# INTERNAL_VCC.net
KiCad netlist of a schematic drawn in EAGLE
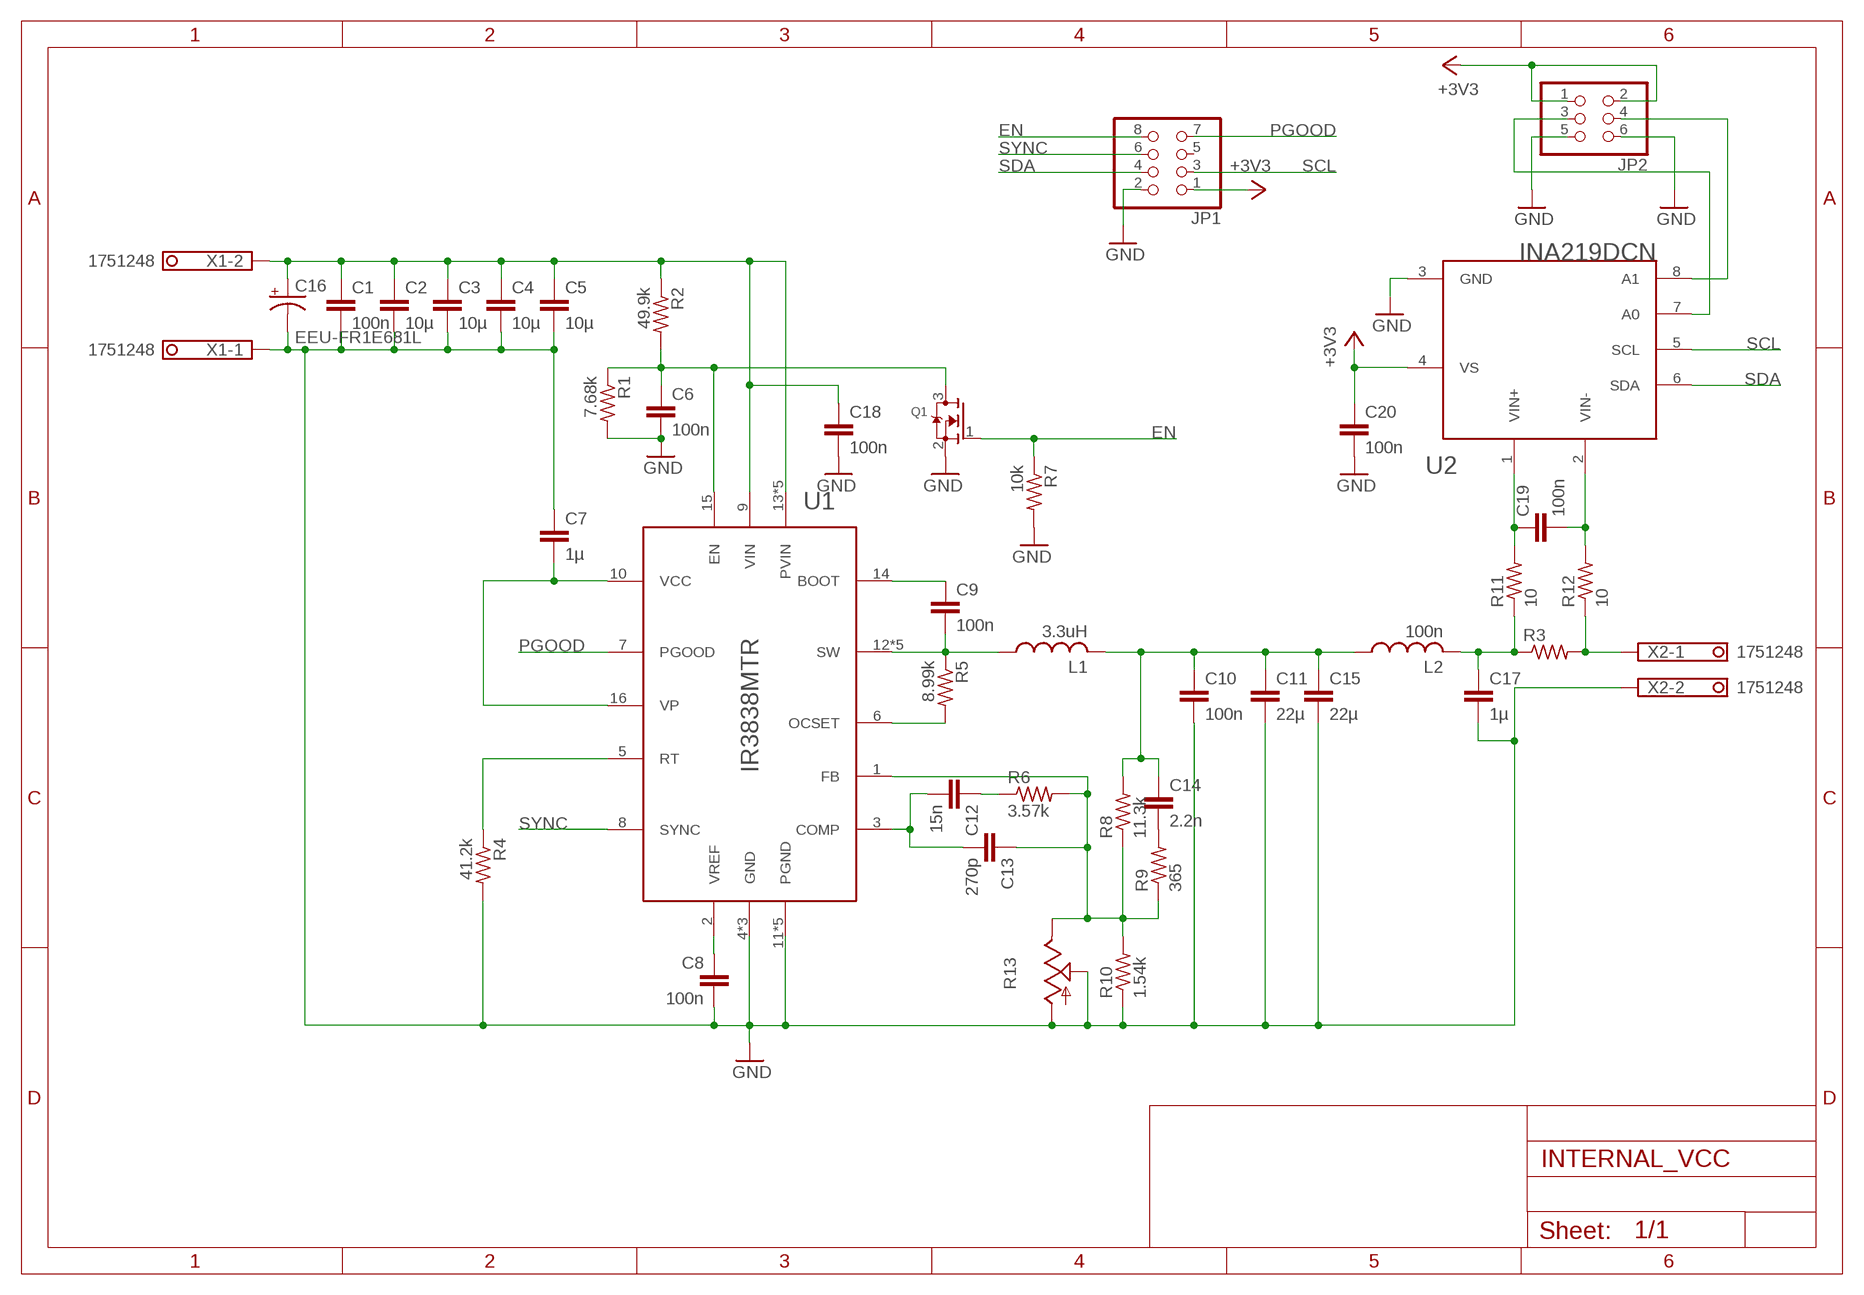
[diagram p0: schematic, sheet 1]

(export (version "E")
  (design (tool "Eeschema 10.0.6"))
  (components
    (comp (ref "C1")
      (value "100n")
      (footprint "eagle-import:C0603")
      (libsource (lib "eagle-import") (part "C-EUC0603"))
    )
    (comp (ref "C2")
      (value "10µ")
      (footprint "eagle-import:C1206")
      (libsource (lib "eagle-import") (part "C-EUC1206"))
    )
    (comp (ref "C3")
      (value "10µ")
      (footprint "eagle-import:C1206")
      (libsource (lib "eagle-import") (part "C-EUC1206"))
    )
    (comp (ref "C4")
      (value "10µ")
      (footprint "eagle-import:C1206")
      (libsource (lib "eagle-import") (part "C-EUC1206"))
    )
    (comp (ref "C5")
      (value "10µ")
      (footprint "eagle-import:C1206")
      (libsource (lib "eagle-import") (part "C-EUC1206"))
    )
    (comp (ref "C6")
      (value "100n")
      (footprint "eagle-import:C0603")
      (libsource (lib "eagle-import") (part "C-EUC0603"))
    )
    (comp (ref "C7")
      (value "1µ")
      (footprint "eagle-import:C0603")
      (libsource (lib "eagle-import") (part "C-EUC0603"))
    )
    (comp (ref "C8")
      (value "100n")
      (footprint "eagle-import:C0603")
      (libsource (lib "eagle-import") (part "C-EUC0603"))
    )
    (comp (ref "C9")
      (value "100n")
      (footprint "eagle-import:C0603")
      (libsource (lib "eagle-import") (part "C-EUC0603"))
    )
    (comp (ref "C10")
      (value "100n")
      (footprint "eagle-import:C0603")
      (libsource (lib "eagle-import") (part "C-EUC0603"))
    )
    (comp (ref "C11")
      (value "22µ")
      (footprint "eagle-import:C1210")
      (libsource (lib "eagle-import") (part "C-EUC1210"))
    )
    (comp (ref "C12")
      (value "15n")
      (footprint "eagle-import:C0603")
      (libsource (lib "eagle-import") (part "C-EUC0603"))
    )
    (comp (ref "C13")
      (value "270p")
      (footprint "eagle-import:C0603")
      (libsource (lib "eagle-import") (part "C-EUC0603"))
    )
    (comp (ref "C14")
      (value "2.2n")
      (footprint "eagle-import:C0603")
      (libsource (lib "eagle-import") (part "C-EUC0603"))
    )
    (comp (ref "C15")
      (value "22µ")
      (footprint "eagle-import:C1210")
      (libsource (lib "eagle-import") (part "C-EUC1210"))
    )
    (comp (ref "C16")
      (value "EEU-FR1E681L")
      (footprint "eagle-import:E3,5-8")
      (libsource (lib "eagle-import") (part "CPOL-USE3.5-8"))
    )
    (comp (ref "C17")
      (value "1µ")
      (footprint "eagle-import:C0603")
      (libsource (lib "eagle-import") (part "C-EUC0603"))
    )
    (comp (ref "C18")
      (value "100n")
      (footprint "eagle-import:C0603")
      (libsource (lib "eagle-import") (part "C-EUC0603"))
    )
    (comp (ref "C19")
      (value "100n")
      (footprint "eagle-import:C0603")
      (libsource (lib "eagle-import") (part "C-EUC0603"))
    )
    (comp (ref "C20")
      (value "100n")
      (footprint "eagle-import:C0603")
      (libsource (lib "eagle-import") (part "C-EUC0603"))
    )
    (comp (ref "JP1")
      (value "PINHD-2X4/90")
      (footprint "eagle-import:2X04_90")
      (libsource (lib "eagle-import") (part "PINHD-2X4/90"))
    )
    (comp (ref "JP2")
      (value "PINHD-2X3")
      (footprint "eagle-import:2X03")
      (libsource (lib "eagle-import") (part "PINHD-2X3"))
    )
    (comp (ref "L1")
      (value "3.3uH")
      (footprint "eagle-import:XAL7070")
      (libsource (lib "eagle-import") (part "L-USXAL7070"))
    )
    (comp (ref "L2")
      (value "100n")
      (footprint "eagle-import:SRP5030CA")
      (libsource (lib "eagle-import") (part "L-USSRP5030CA"))
    )
    (comp (ref "Q1")
      (value "MOSFET-NREFLOW")
      (footprint "eagle-import:SOT23")
      (libsource (lib "eagle-import") (part "MOSFET-NREFLOW"))
    )
    (comp (ref "R1")
      (value "7.68k")
      (footprint "eagle-import:R0603")
      (libsource (lib "eagle-import") (part "R-US_R0603"))
    )
    (comp (ref "R2")
      (value "49.9k")
      (footprint "eagle-import:R0603")
      (libsource (lib "eagle-import") (part "R-US_R0603"))
    )
    (comp (ref "R3")
      (value "R-US_R2010")
      (footprint "eagle-import:R2010")
      (libsource (lib "eagle-import") (part "R-US_R2010"))
    )
    (comp (ref "R4")
      (value "41.2k")
      (footprint "eagle-import:R0603")
      (libsource (lib "eagle-import") (part "R-US_R0603"))
    )
    (comp (ref "R5")
      (value "8.99k")
      (footprint "eagle-import:R0603")
      (libsource (lib "eagle-import") (part "R-US_R0603"))
    )
    (comp (ref "R6")
      (value "3.57k")
      (footprint "eagle-import:R0603")
      (libsource (lib "eagle-import") (part "R-US_R0603"))
    )
    (comp (ref "R7")
      (value "10k")
      (footprint "eagle-import:R0603")
      (libsource (lib "eagle-import") (part "R-US_R0603"))
    )
    (comp (ref "R8")
      (value "11.3k")
      (footprint "eagle-import:R0603")
      (libsource (lib "eagle-import") (part "R-US_R0603"))
    )
    (comp (ref "R9")
      (value "365")
      (footprint "eagle-import:R0603")
      (libsource (lib "eagle-import") (part "R-US_R0603"))
    )
    (comp (ref "R10")
      (value "1.54k")
      (footprint "eagle-import:R0603")
      (libsource (lib "eagle-import") (part "R-US_R0603"))
    )
    (comp (ref "R11")
      (value "10")
      (footprint "eagle-import:R0603")
      (libsource (lib "eagle-import") (part "R-US_R0603"))
    )
    (comp (ref "R12")
      (value "10")
      (footprint "eagle-import:R0603")
      (libsource (lib "eagle-import") (part "R-US_R0603"))
    )
    (comp (ref "R13")
      (value "TRIM_US-B25P")
      (footprint "eagle-import:B25P")
      (libsource (lib "eagle-import") (part "TRIM_US-B25P"))
    )
    (comp (ref "U1")
      (value "IR3838MTR")
      (footprint "eagle-import:PQFN_5X6_MM")
      (libsource (lib "eagle-import") (part "IR3838MTR"))
    )
    (comp (ref "U2")
      (value "INA219DCN")
      (footprint "eagle-import:DCN-R-PDSO-G8")
      (libsource (lib "eagle-import") (part "INA219DCN"))
    )
    (comp (ref "X1")
      (value "1751248")
      (footprint "eagle-import:1751248")
      (libsource (lib "eagle-import") (part "1751248"))
    )
    (comp (ref "X2")
      (value "1751248")
      (footprint "eagle-import:1751248")
      (libsource (lib "eagle-import") (part "1751248"))
    )
  )
  (nets
    (net (code "1") (name "+3V3") (class "Default")
      (node (ref "C20") (pin "1") (pinfunction "1_1") (pintype "passive"))
      (node (ref "JP1") (pin "1") (pinfunction "1_1") (pintype "passive"))
      (node (ref "JP2") (pin "1") (pinfunction "1_1") (pintype "passive"))
      (node (ref "JP2") (pin "2") (pinfunction "2_2") (pintype "passive"))
      (node (ref "U2") (pin "4") (pinfunction "VS_4") (pintype "bidirectional"))
    )
    (net (code "2") (name "/EN") (class "Default")
      (node (ref "JP1") (pin "8") (pinfunction "8_8") (pintype "passive"))
      (node (ref "Q1") (pin "1") (pinfunction "G_1") (pintype "bidirectional"))
      (node (ref "R7") (pin "1") (pinfunction "1_1") (pintype "passive"))
    )
    (net (code "3") (name "/PGOOD") (class "Default")
      (node (ref "JP1") (pin "7") (pinfunction "7_7") (pintype "passive"))
      (node (ref "U1") (pin "7") (pinfunction "PGOOD_7") (pintype "bidirectional"))
    )
    (net (code "4") (name "/SCL") (class "Default")
      (node (ref "JP1") (pin "3") (pinfunction "3_3") (pintype "passive"))
      (node (ref "U2") (pin "5") (pinfunction "SCL_5") (pintype "bidirectional"))
    )
    (net (code "5") (name "/SDA") (class "Default")
      (node (ref "JP1") (pin "4") (pinfunction "4_4") (pintype "passive"))
      (node (ref "U2") (pin "6") (pinfunction "SDA_6") (pintype "bidirectional"))
    )
    (net (code "6") (name "/SYNC") (class "Default")
      (node (ref "JP1") (pin "6") (pinfunction "6_6") (pintype "passive"))
      (node (ref "U1") (pin "8") (pinfunction "SYNC_8") (pintype "bidirectional"))
    )
    (net (code "7") (name "GND") (class "Default")
      (node (ref "C1") (pin "2") (pinfunction "2_2") (pintype "passive"))
      (node (ref "C10") (pin "2") (pinfunction "2_2") (pintype "passive"))
      (node (ref "C11") (pin "2") (pinfunction "2_2") (pintype "passive"))
      (node (ref "C15") (pin "2") (pinfunction "2_2") (pintype "passive"))
      (node (ref "C16") (pin "-") (pinfunction "-_-") (pintype "passive"))
      (node (ref "C17") (pin "2") (pinfunction "2_2") (pintype "passive"))
      (node (ref "C18") (pin "2") (pinfunction "2_2") (pintype "passive"))
      (node (ref "C2") (pin "2") (pinfunction "2_2") (pintype "passive"))
      (node (ref "C20") (pin "2") (pinfunction "2_2") (pintype "passive"))
      (node (ref "C3") (pin "2") (pinfunction "2_2") (pintype "passive"))
      (node (ref "C4") (pin "2") (pinfunction "2_2") (pintype "passive"))
      (node (ref "C5") (pin "2") (pinfunction "2_2") (pintype "passive"))
      (node (ref "C6") (pin "2") (pinfunction "2_2") (pintype "passive"))
      (node (ref "C7") (pin "1") (pinfunction "1_1") (pintype "passive"))
      (node (ref "C8") (pin "2") (pinfunction "2_2") (pintype "passive"))
      (node (ref "JP1") (pin "2") (pinfunction "2_2") (pintype "passive"))
      (node (ref "JP2") (pin "5") (pinfunction "5_5") (pintype "passive"))
      (node (ref "JP2") (pin "6") (pinfunction "6_6") (pintype "passive"))
      (node (ref "Q1") (pin "2") (pinfunction "S_2") (pintype "bidirectional"))
      (node (ref "R1") (pin "2") (pinfunction "2_2") (pintype "passive"))
      (node (ref "R10") (pin "1") (pinfunction "1_1") (pintype "passive"))
      (node (ref "R13") (pin "A") (pinfunction "A_A") (pintype "passive"))
      (node (ref "R13") (pin "S") (pinfunction "S_S") (pintype "passive"))
      (node (ref "R4") (pin "2") (pinfunction "2_2") (pintype "passive"))
      (node (ref "R7") (pin "2") (pinfunction "2_2") (pintype "passive"))
      (node (ref "U1") (pin "11") (pinfunction "PGND_11") (pintype "bidirectional"))
      (node (ref "U1") (pin "11@1") (pinfunction "PGND_11@1") (pintype "bidirectional"))
      (node (ref "U1") (pin "11@2") (pinfunction "PGND_11@2") (pintype "bidirectional"))
      (node (ref "U1") (pin "11@3") (pinfunction "PGND_11@3") (pintype "bidirectional"))
      (node (ref "U1") (pin "11@4") (pinfunction "PGND_11@4") (pintype "bidirectional"))
      (node (ref "U1") (pin "4") (pinfunction "GND_4") (pintype "bidirectional"))
      (node (ref "U1") (pin "P$1") (pinfunction "GND_P$1") (pintype "bidirectional"))
      (node (ref "U1") (pin "P$26") (pinfunction "GND_P$26") (pintype "bidirectional"))
      (node (ref "U2") (pin "3") (pinfunction "GND_3") (pintype "bidirectional"))
      (node (ref "X1") (pin "1") (pinfunction "K_1") (pintype "passive"))
      (node (ref "X2") (pin "2") (pinfunction "K_2") (pintype "passive"))
    )
    (net (code "8") (name "Net-(C9-Pad2)") (class "Default")
      (node (ref "C9") (pin "2") (pinfunction "2_2") (pintype "passive"))
      (node (ref "L1") (pin "1") (pinfunction "1_1") (pintype "passive"))
      (node (ref "L1") (pin "3") (pinfunction "1_3") (pintype "passive"))
      (node (ref "R5") (pin "1") (pinfunction "1_1") (pintype "passive"))
      (node (ref "U1") (pin "12") (pinfunction "SW_12") (pintype "bidirectional"))
      (node (ref "U1") (pin "12@1") (pinfunction "SW_12@1") (pintype "bidirectional"))
      (node (ref "U1") (pin "12@2") (pinfunction "SW_12@2") (pintype "bidirectional"))
      (node (ref "U1") (pin "12@3") (pinfunction "SW_12@3") (pintype "bidirectional"))
      (node (ref "U1") (pin "12@4") (pinfunction "SW_12@4") (pintype "bidirectional"))
    )
    (net (code "9") (name "Net-(C10-Pad1)") (class "Default")
      (node (ref "C10") (pin "1") (pinfunction "1_1") (pintype "passive"))
      (node (ref "C11") (pin "1") (pinfunction "1_1") (pintype "passive"))
      (node (ref "C14") (pin "1") (pinfunction "1_1") (pintype "passive"))
      (node (ref "C15") (pin "1") (pinfunction "1_1") (pintype "passive"))
      (node (ref "L1") (pin "2") (pinfunction "2_2") (pintype "passive"))
      (node (ref "L1") (pin "4") (pinfunction "2_4") (pintype "passive"))
      (node (ref "L2") (pin "1") (pinfunction "1_1") (pintype "passive"))
      (node (ref "R8") (pin "2") (pinfunction "2_2") (pintype "passive"))
    )
    (net (code "10") (name "Net-(C12-Pad1)") (class "Default")
      (node (ref "C12") (pin "1") (pinfunction "1_1") (pintype "passive"))
      (node (ref "R6") (pin "1") (pinfunction "1_1") (pintype "passive"))
    )
    (net (code "11") (name "Net-(C14-Pad2)") (class "Default")
      (node (ref "C14") (pin "2") (pinfunction "2_2") (pintype "passive"))
      (node (ref "R9") (pin "2") (pinfunction "2_2") (pintype "passive"))
    )
    (net (code "12") (name "Net-(C17-Pad1)") (class "Default")
      (node (ref "C17") (pin "1") (pinfunction "1_1") (pintype "passive"))
      (node (ref "L2") (pin "2") (pinfunction "2_2") (pintype "passive"))
      (node (ref "R11") (pin "1") (pinfunction "1_1") (pintype "passive"))
      (node (ref "R3") (pin "1") (pinfunction "1_1") (pintype "passive"))
    )
    (net (code "13") (name "Net-(Q1-D)") (class "Default")
      (node (ref "C6") (pin "1") (pinfunction "1_1") (pintype "passive"))
      (node (ref "Q1") (pin "3") (pinfunction "D_3") (pintype "bidirectional"))
      (node (ref "R1") (pin "1") (pinfunction "1_1") (pintype "passive"))
      (node (ref "R2") (pin "2") (pinfunction "2_2") (pintype "passive"))
      (node (ref "U1") (pin "15") (pinfunction "EN_15") (pintype "bidirectional"))
    )
    (net (code "14") (name "Net-(U1-BOOT)") (class "Default")
      (node (ref "C9") (pin "1") (pinfunction "1_1") (pintype "passive"))
      (node (ref "U1") (pin "14") (pinfunction "BOOT_14") (pintype "bidirectional"))
    )
    (net (code "15") (name "Net-(U1-COMP)") (class "Default")
      (node (ref "C12") (pin "2") (pinfunction "2_2") (pintype "passive"))
      (node (ref "C13") (pin "2") (pinfunction "2_2") (pintype "passive"))
      (node (ref "U1") (pin "3") (pinfunction "COMP_3") (pintype "bidirectional"))
    )
    (net (code "16") (name "Net-(U1-FB)") (class "Default")
      (node (ref "C13") (pin "1") (pinfunction "1_1") (pintype "passive"))
      (node (ref "R10") (pin "2") (pinfunction "2_2") (pintype "passive"))
      (node (ref "R13") (pin "E") (pinfunction "E_E") (pintype "passive"))
      (node (ref "R6") (pin "2") (pinfunction "2_2") (pintype "passive"))
      (node (ref "R8") (pin "1") (pinfunction "1_1") (pintype "passive"))
      (node (ref "R9") (pin "1") (pinfunction "1_1") (pintype "passive"))
      (node (ref "U1") (pin "1") (pinfunction "FB_1") (pintype "bidirectional"))
    )
    (net (code "17") (name "Net-(U1-OCSET)") (class "Default")
      (node (ref "R5") (pin "2") (pinfunction "2_2") (pintype "passive"))
      (node (ref "U1") (pin "6") (pinfunction "OCSET_6") (pintype "bidirectional"))
    )
    (net (code "18") (name "Net-(U1-RT)") (class "Default")
      (node (ref "R4") (pin "1") (pinfunction "1_1") (pintype "passive"))
      (node (ref "U1") (pin "5") (pinfunction "RT_5") (pintype "bidirectional"))
    )
    (net (code "19") (name "Net-(U1-VCC)") (class "Default")
      (node (ref "C7") (pin "2") (pinfunction "2_2") (pintype "passive"))
      (node (ref "U1") (pin "10") (pinfunction "VCC_10") (pintype "bidirectional"))
      (node (ref "U1") (pin "16") (pinfunction "VP_16") (pintype "bidirectional"))
    )
    (net (code "20") (name "Net-(U1-VIN)") (class "Default")
      (node (ref "C1") (pin "1") (pinfunction "1_1") (pintype "passive"))
      (node (ref "C16") (pin "+") (pinfunction "+_+") (pintype "passive"))
      (node (ref "C18") (pin "1") (pinfunction "1_1") (pintype "passive"))
      (node (ref "C2") (pin "1") (pinfunction "1_1") (pintype "passive"))
      (node (ref "C3") (pin "1") (pinfunction "1_1") (pintype "passive"))
      (node (ref "C4") (pin "1") (pinfunction "1_1") (pintype "passive"))
      (node (ref "C5") (pin "1") (pinfunction "1_1") (pintype "passive"))
      (node (ref "R2") (pin "1") (pinfunction "1_1") (pintype "passive"))
      (node (ref "U1") (pin "13") (pinfunction "PVIN_13") (pintype "bidirectional"))
      (node (ref "U1") (pin "13@1") (pinfunction "PVIN_13@1") (pintype "bidirectional"))
      (node (ref "U1") (pin "13@2") (pinfunction "PVIN_13@2") (pintype "bidirectional"))
      (node (ref "U1") (pin "13@3") (pinfunction "PVIN_13@3") (pintype "bidirectional"))
      (node (ref "U1") (pin "13@4") (pinfunction "PVIN_13@4") (pintype "bidirectional"))
      (node (ref "U1") (pin "9") (pinfunction "VIN_9") (pintype "bidirectional"))
      (node (ref "X1") (pin "2") (pinfunction "K_2") (pintype "passive"))
    )
    (net (code "21") (name "Net-(U1-VREF)") (class "Default")
      (node (ref "C8") (pin "1") (pinfunction "1_1") (pintype "passive"))
      (node (ref "U1") (pin "2") (pinfunction "VREF_2") (pintype "bidirectional"))
    )
    (net (code "22") (name "Net-(U2-A0)") (class "Default")
      (node (ref "JP2") (pin "3") (pinfunction "3_3") (pintype "passive"))
      (node (ref "U2") (pin "7") (pinfunction "A0_7") (pintype "bidirectional"))
    )
    (net (code "23") (name "Net-(U2-A1)") (class "Default")
      (node (ref "JP2") (pin "4") (pinfunction "4_4") (pintype "passive"))
      (node (ref "U2") (pin "8") (pinfunction "A1_8") (pintype "bidirectional"))
    )
    (net (code "24") (name "Net-(U2-VIN+)") (class "Default")
      (node (ref "C19") (pin "1") (pinfunction "1_1") (pintype "passive"))
      (node (ref "R11") (pin "2") (pinfunction "2_2") (pintype "passive"))
      (node (ref "U2") (pin "1") (pinfunction "VIN+_1") (pintype "bidirectional"))
    )
    (net (code "25") (name "Net-(U2-VIN-)") (class "Default")
      (node (ref "C19") (pin "2") (pinfunction "2_2") (pintype "passive"))
      (node (ref "R12") (pin "2") (pinfunction "2_2") (pintype "passive"))
      (node (ref "U2") (pin "2") (pinfunction "VIN-_2") (pintype "bidirectional"))
    )
    (net (code "26") (name "Net-(X2A-K)") (class "Default")
      (node (ref "R12") (pin "1") (pinfunction "1_1") (pintype "passive"))
      (node (ref "R3") (pin "2") (pinfunction "2_2") (pintype "passive"))
      (node (ref "X2") (pin "1") (pinfunction "K_1") (pintype "passive"))
    )
    (net (code "27") (name "unconnected-(JP1-Pad5)") (class "Default")
      (node (ref "JP1") (pin "5") (pinfunction "5_5") (pintype "passive"))
    )
  )
)
